# GPIO_Hat_v4_0_assignment.net
KiCad netlist of a schematic drawn in EAGLE
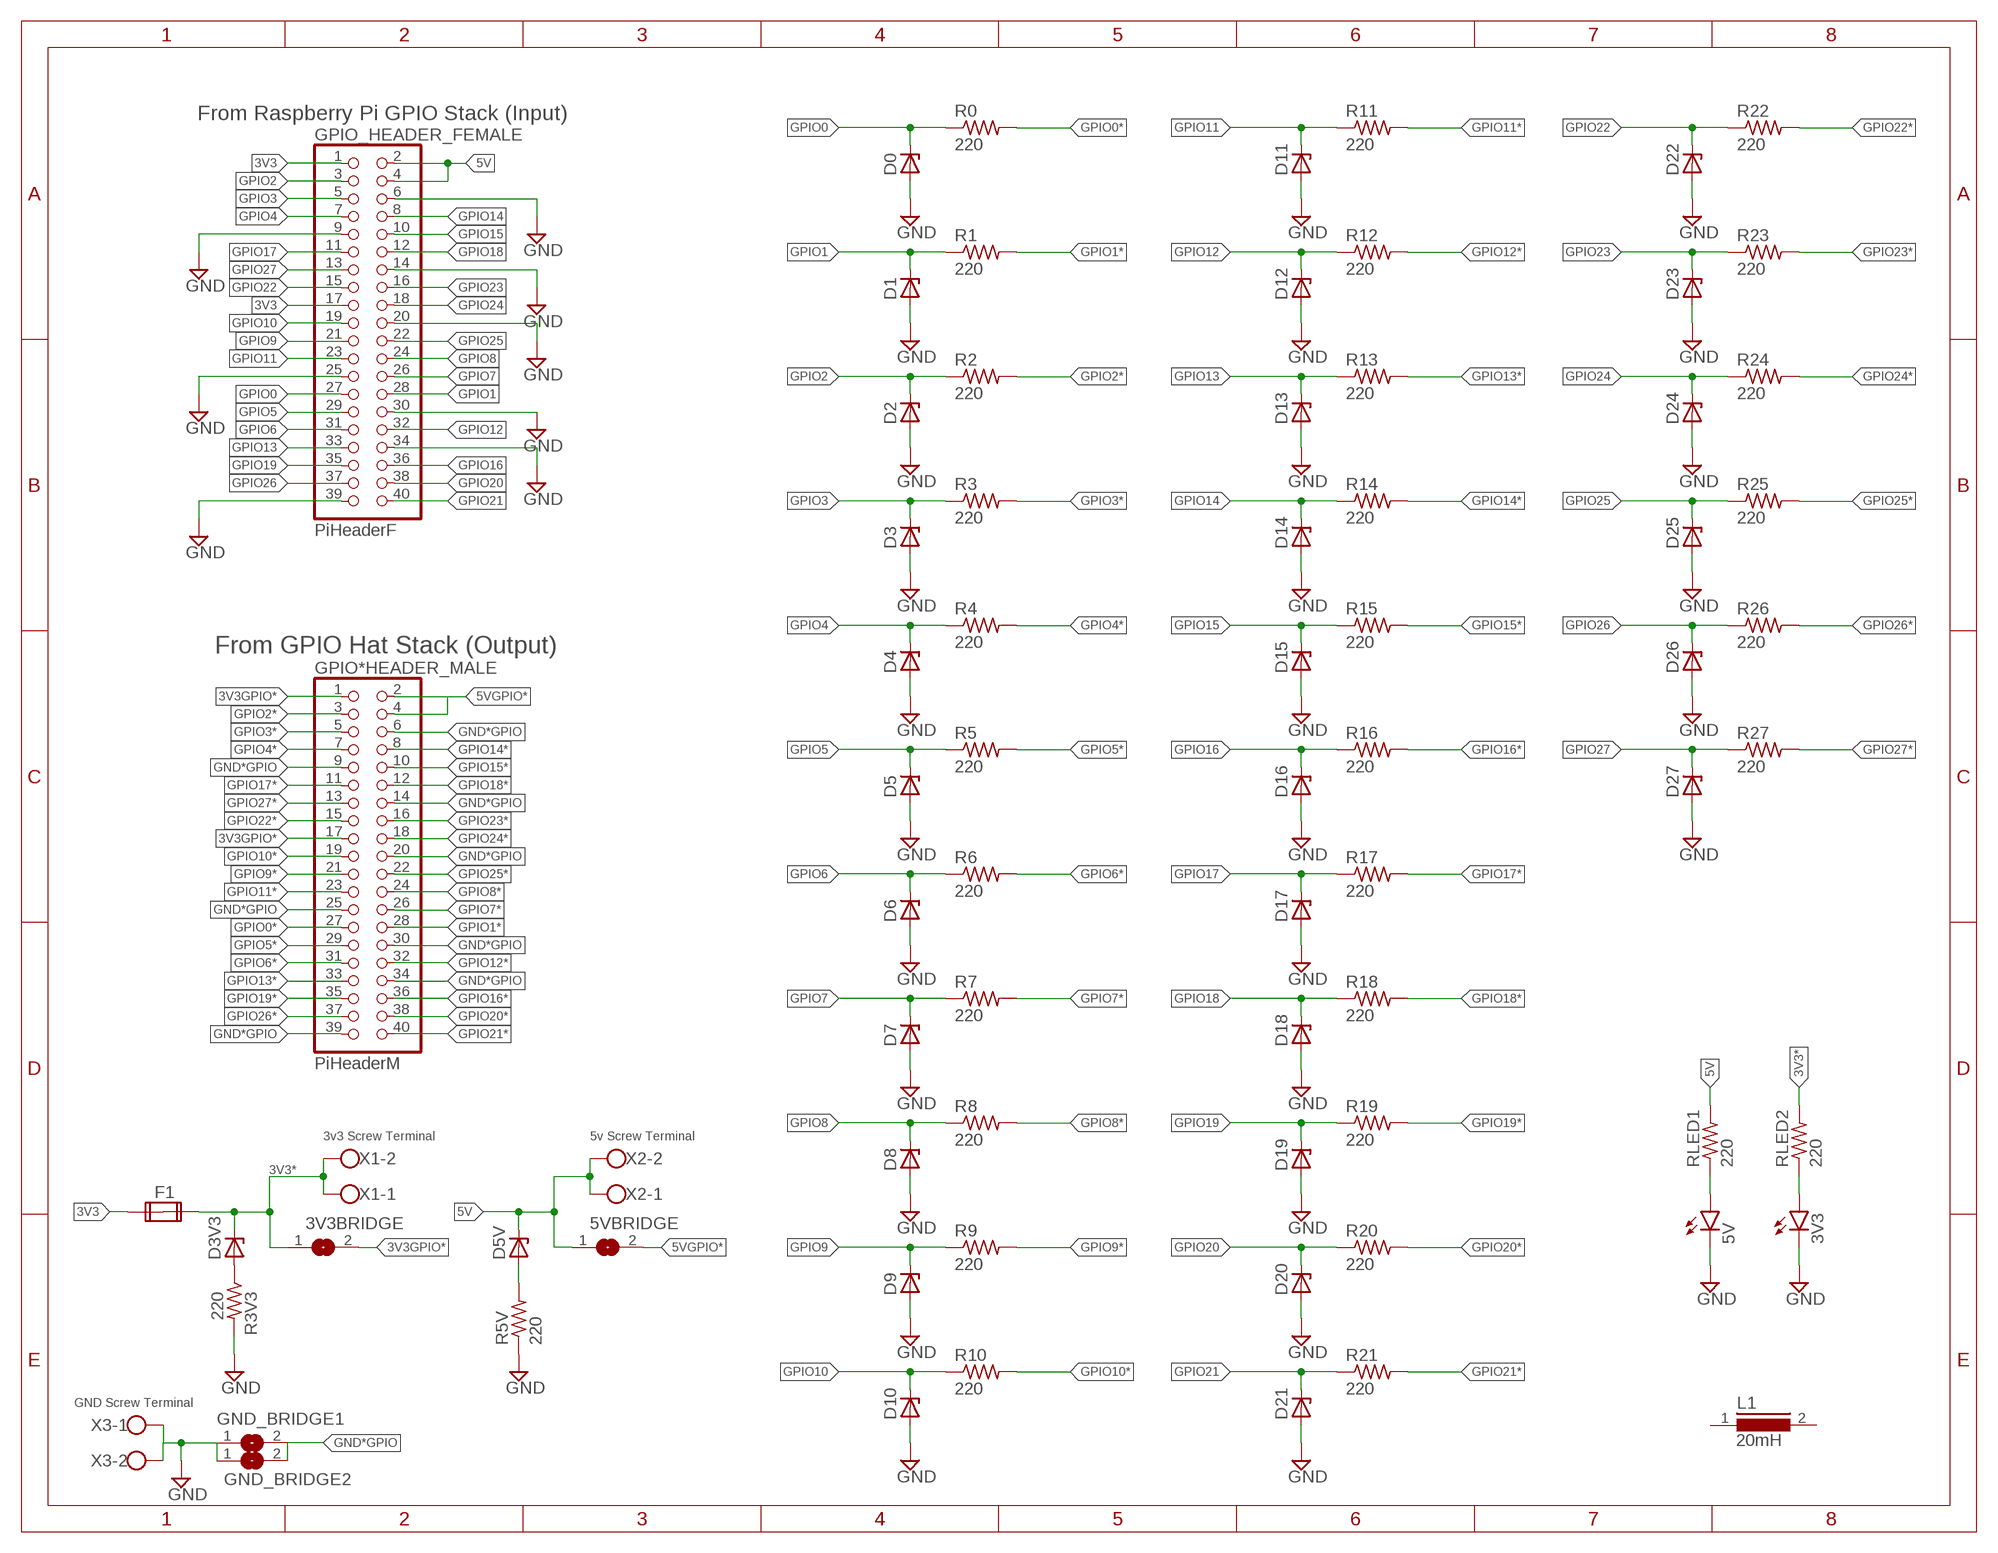
[diagram p0: schematic, sheet 1]

(export (version "E")
  (design (tool "Eeschema 10.0.6"))
  (components
    (comp (ref "3V3")
      (value "LED5MM")
      (footprint "eagle-import:LED5MM")
      (libsource (lib "eagle-import") (part "LED5MM"))
    )
    (comp (ref "3V3BRIDGE")
      (value "SJ")
      (footprint "eagle-import:SJ")
      (libsource (lib "eagle-import") (part "SJ"))
    )
    (comp (ref "5V")
      (value "LED5MM")
      (footprint "eagle-import:LED5MM")
      (libsource (lib "eagle-import") (part "LED5MM"))
    )
    (comp (ref "5VBRIDGE")
      (value "SJ")
      (footprint "eagle-import:SJ")
      (libsource (lib "eagle-import") (part "SJ"))
    )
    (comp (ref "D0")
      (value "1N4728")
      (footprint "eagle-import:DO41Z10")
      (fields (field (name "MF") "ON Semiconductor"))
      (libsource (lib "eagle-import") (part "1N4728"))
    )
    (comp (ref "D1")
      (value "1N4728")
      (footprint "eagle-import:DO41Z10")
      (fields (field (name "MF") "ON Semiconductor"))
      (libsource (lib "eagle-import") (part "1N4728"))
    )
    (comp (ref "D2")
      (value "1N4728")
      (footprint "eagle-import:DO41Z10")
      (fields (field (name "MF") "ON Semiconductor"))
      (libsource (lib "eagle-import") (part "1N4728"))
    )
    (comp (ref "D3")
      (value "1N4728")
      (footprint "eagle-import:DO41Z10")
      (fields (field (name "MF") "ON Semiconductor"))
      (libsource (lib "eagle-import") (part "1N4728"))
    )
    (comp (ref "D3V3")
      (value "1N4728")
      (footprint "eagle-import:DO41Z10")
      (fields (field (name "MF") "ON Semiconductor"))
      (libsource (lib "eagle-import") (part "1N4728"))
    )
    (comp (ref "D4")
      (value "1N4728")
      (footprint "eagle-import:DO41Z10")
      (fields (field (name "MF") "ON Semiconductor"))
      (libsource (lib "eagle-import") (part "1N4728"))
    )
    (comp (ref "D5")
      (value "1N4728")
      (footprint "eagle-import:DO41Z10")
      (fields (field (name "MF") "ON Semiconductor"))
      (libsource (lib "eagle-import") (part "1N4728"))
    )
    (comp (ref "D5V")
      (value "1N4728")
      (footprint "eagle-import:DO41Z10")
      (fields (field (name "MF") "ON Semiconductor"))
      (libsource (lib "eagle-import") (part "1N4728"))
    )
    (comp (ref "D6")
      (value "1N4728")
      (footprint "eagle-import:DO41Z10")
      (fields (field (name "MF") "ON Semiconductor"))
      (libsource (lib "eagle-import") (part "1N4728"))
    )
    (comp (ref "D7")
      (value "1N4728")
      (footprint "eagle-import:DO41Z10")
      (fields (field (name "MF") "ON Semiconductor"))
      (libsource (lib "eagle-import") (part "1N4728"))
    )
    (comp (ref "D8")
      (value "1N4728")
      (footprint "eagle-import:DO41Z10")
      (fields (field (name "MF") "ON Semiconductor"))
      (libsource (lib "eagle-import") (part "1N4728"))
    )
    (comp (ref "D9")
      (value "1N4728")
      (footprint "eagle-import:DO41Z10")
      (fields (field (name "MF") "ON Semiconductor"))
      (libsource (lib "eagle-import") (part "1N4728"))
    )
    (comp (ref "D10")
      (value "1N4728")
      (footprint "eagle-import:DO41Z10")
      (fields (field (name "MF") "ON Semiconductor"))
      (libsource (lib "eagle-import") (part "1N4728"))
    )
    (comp (ref "D11")
      (value "1N4728")
      (footprint "eagle-import:DO41Z10")
      (fields (field (name "MF") "ON Semiconductor"))
      (libsource (lib "eagle-import") (part "1N4728"))
    )
    (comp (ref "D12")
      (value "1N4728")
      (footprint "eagle-import:DO41Z10")
      (fields (field (name "MF") "ON Semiconductor"))
      (libsource (lib "eagle-import") (part "1N4728"))
    )
    (comp (ref "D13")
      (value "1N4728")
      (footprint "eagle-import:DO41Z10")
      (fields (field (name "MF") "ON Semiconductor"))
      (libsource (lib "eagle-import") (part "1N4728"))
    )
    (comp (ref "D14")
      (value "1N4728")
      (footprint "eagle-import:DO41Z10")
      (fields (field (name "MF") "ON Semiconductor"))
      (libsource (lib "eagle-import") (part "1N4728"))
    )
    (comp (ref "D15")
      (value "1N4728")
      (footprint "eagle-import:DO41Z10")
      (fields (field (name "MF") "ON Semiconductor"))
      (libsource (lib "eagle-import") (part "1N4728"))
    )
    (comp (ref "D16")
      (value "1N4728")
      (footprint "eagle-import:DO41Z10")
      (fields (field (name "MF") "ON Semiconductor"))
      (libsource (lib "eagle-import") (part "1N4728"))
    )
    (comp (ref "D17")
      (value "1N4728")
      (footprint "eagle-import:DO41Z10")
      (fields (field (name "MF") "ON Semiconductor"))
      (libsource (lib "eagle-import") (part "1N4728"))
    )
    (comp (ref "D18")
      (value "1N4728")
      (footprint "eagle-import:DO41Z10")
      (fields (field (name "MF") "ON Semiconductor"))
      (libsource (lib "eagle-import") (part "1N4728"))
    )
    (comp (ref "D19")
      (value "1N4728")
      (footprint "eagle-import:DO41Z10")
      (fields (field (name "MF") "ON Semiconductor"))
      (libsource (lib "eagle-import") (part "1N4728"))
    )
    (comp (ref "D20")
      (value "1N4728")
      (footprint "eagle-import:DO41Z10")
      (fields (field (name "MF") "ON Semiconductor"))
      (libsource (lib "eagle-import") (part "1N4728"))
    )
    (comp (ref "D21")
      (value "1N4728")
      (footprint "eagle-import:DO41Z10")
      (fields (field (name "MF") "ON Semiconductor"))
      (libsource (lib "eagle-import") (part "1N4728"))
    )
    (comp (ref "D22")
      (value "1N4728")
      (footprint "eagle-import:DO41Z10")
      (fields (field (name "MF") "ON Semiconductor"))
      (libsource (lib "eagle-import") (part "1N4728"))
    )
    (comp (ref "D23")
      (value "1N4728")
      (footprint "eagle-import:DO41Z10")
      (fields (field (name "MF") "ON Semiconductor"))
      (libsource (lib "eagle-import") (part "1N4728"))
    )
    (comp (ref "D24")
      (value "1N4728")
      (footprint "eagle-import:DO41Z10")
      (fields (field (name "MF") "ON Semiconductor"))
      (libsource (lib "eagle-import") (part "1N4728"))
    )
    (comp (ref "D25")
      (value "1N4728")
      (footprint "eagle-import:DO41Z10")
      (fields (field (name "MF") "ON Semiconductor"))
      (libsource (lib "eagle-import") (part "1N4728"))
    )
    (comp (ref "D26")
      (value "1N4728")
      (footprint "eagle-import:DO41Z10")
      (fields (field (name "MF") "ON Semiconductor"))
      (libsource (lib "eagle-import") (part "1N4728"))
    )
    (comp (ref "D27")
      (value "1N4728")
      (footprint "eagle-import:DO41Z10")
      (fields (field (name "MF") "ON Semiconductor"))
      (libsource (lib "eagle-import") (part "1N4728"))
    )
    (comp (ref "F1")
      (value "FUSE2P")
      (footprint "eagle-import:FUSE1")
      (libsource (lib "eagle-import") (part "FUSE2P"))
    )
    (comp (ref "GND_BRIDGE1")
      (value "SJ")
      (footprint "eagle-import:SJ")
      (libsource (lib "eagle-import") (part "SJ"))
    )
    (comp (ref "GND_BRIDGE2")
      (value "SJ")
      (footprint "eagle-import:SJ")
      (libsource (lib "eagle-import") (part "SJ"))
    )
    (comp (ref "GPIO*HEADER_MALE")
      (value "PiHeaderM")
      (footprint "eagle-import:2X20")
      (libsource (lib "eagle-import") (part "PINHD-2X20"))
    )
    (comp (ref "GPIO_HEADER_FEMALE")
      (value "PiHeaderF")
      (footprint "eagle-import:2X20")
      (libsource (lib "eagle-import") (part "PINHD-2X20"))
    )
    (comp (ref "L1")
      (value "20mH")
      (footprint "eagle-import:A26GFC")
      (libsource (lib "eagle-import") (part "A26GFC"))
    )
    (comp (ref "R0")
      (value "220")
      (footprint "eagle-import:0207_10")
      (libsource (lib "eagle-import") (part "rcl_334_R-US_0207/10"))
    )
    (comp (ref "R1")
      (value "220")
      (footprint "eagle-import:0207_10")
      (libsource (lib "eagle-import") (part "rcl_334_R-US_0207/10"))
    )
    (comp (ref "R2")
      (value "220")
      (footprint "eagle-import:0207_10")
      (libsource (lib "eagle-import") (part "rcl_334_R-US_0207/10"))
    )
    (comp (ref "R3")
      (value "220")
      (footprint "eagle-import:0207_10")
      (libsource (lib "eagle-import") (part "rcl_334_R-US_0207/10"))
    )
    (comp (ref "R3V3")
      (value "220")
      (footprint "eagle-import:0207_10")
      (libsource (lib "eagle-import") (part "rcl_334_R-US_0207/10"))
    )
    (comp (ref "R4")
      (value "220")
      (footprint "eagle-import:0207_10")
      (libsource (lib "eagle-import") (part "rcl_334_R-US_0207/10"))
    )
    (comp (ref "R5")
      (value "220")
      (footprint "eagle-import:0207_10")
      (libsource (lib "eagle-import") (part "rcl_334_R-US_0207/10"))
    )
    (comp (ref "R5V")
      (value "220")
      (footprint "eagle-import:0207_10")
      (libsource (lib "eagle-import") (part "rcl_334_R-US_0207/10"))
    )
    (comp (ref "R6")
      (value "220")
      (footprint "eagle-import:0207_10")
      (libsource (lib "eagle-import") (part "rcl_334_R-US_0207/10"))
    )
    (comp (ref "R7")
      (value "220")
      (footprint "eagle-import:0207_10")
      (libsource (lib "eagle-import") (part "rcl_334_R-US_0207/10"))
    )
    (comp (ref "R8")
      (value "220")
      (footprint "eagle-import:0207_10")
      (libsource (lib "eagle-import") (part "rcl_334_R-US_0207/10"))
    )
    (comp (ref "R9")
      (value "220")
      (footprint "eagle-import:0207_10")
      (libsource (lib "eagle-import") (part "rcl_334_R-US_0207/10"))
    )
    (comp (ref "R10")
      (value "220")
      (footprint "eagle-import:0207_10")
      (libsource (lib "eagle-import") (part "rcl_334_R-US_0207/10"))
    )
    (comp (ref "R11")
      (value "220")
      (footprint "eagle-import:0207_10")
      (libsource (lib "eagle-import") (part "rcl_334_R-US_0207/10"))
    )
    (comp (ref "R12")
      (value "220")
      (footprint "eagle-import:0207_10")
      (libsource (lib "eagle-import") (part "rcl_334_R-US_0207/10"))
    )
    (comp (ref "R13")
      (value "220")
      (footprint "eagle-import:0207_10")
      (libsource (lib "eagle-import") (part "rcl_334_R-US_0207/10"))
    )
    (comp (ref "R14")
      (value "220")
      (footprint "eagle-import:0207_10")
      (libsource (lib "eagle-import") (part "rcl_334_R-US_0207/10"))
    )
    (comp (ref "R15")
      (value "220")
      (footprint "eagle-import:0207_10")
      (libsource (lib "eagle-import") (part "rcl_334_R-US_0207/10"))
    )
    (comp (ref "R16")
      (value "220")
      (footprint "eagle-import:0207_10")
      (libsource (lib "eagle-import") (part "rcl_334_R-US_0207/10"))
    )
    (comp (ref "R17")
      (value "220")
      (footprint "eagle-import:0207_10")
      (libsource (lib "eagle-import") (part "rcl_334_R-US_0207/10"))
    )
    (comp (ref "R18")
      (value "220")
      (footprint "eagle-import:0207_10")
      (libsource (lib "eagle-import") (part "rcl_334_R-US_0207/10"))
    )
    (comp (ref "R19")
      (value "220")
      (footprint "eagle-import:0207_10")
      (libsource (lib "eagle-import") (part "rcl_334_R-US_0207/10"))
    )
    (comp (ref "R20")
      (value "220")
      (footprint "eagle-import:0207_10")
      (libsource (lib "eagle-import") (part "rcl_334_R-US_0207/10"))
    )
    (comp (ref "R21")
      (value "220")
      (footprint "eagle-import:0207_10")
      (libsource (lib "eagle-import") (part "rcl_334_R-US_0207/10"))
    )
    (comp (ref "R22")
      (value "220")
      (footprint "eagle-import:0207_10")
      (libsource (lib "eagle-import") (part "rcl_334_R-US_0207/10"))
    )
    (comp (ref "R23")
      (value "220")
      (footprint "eagle-import:0207_10")
      (libsource (lib "eagle-import") (part "rcl_334_R-US_0207/10"))
    )
    (comp (ref "R24")
      (value "220")
      (footprint "eagle-import:0207_10")
      (libsource (lib "eagle-import") (part "rcl_334_R-US_0207/10"))
    )
    (comp (ref "R25")
      (value "220")
      (footprint "eagle-import:0207_10")
      (libsource (lib "eagle-import") (part "rcl_334_R-US_0207/10"))
    )
    (comp (ref "R26")
      (value "220")
      (footprint "eagle-import:0207_10")
      (libsource (lib "eagle-import") (part "rcl_334_R-US_0207/10"))
    )
    (comp (ref "R27")
      (value "220")
      (footprint "eagle-import:0207_10")
      (libsource (lib "eagle-import") (part "rcl_334_R-US_0207/10"))
    )
    (comp (ref "RLED1")
      (value "220")
      (footprint "eagle-import:0207_10")
      (libsource (lib "eagle-import") (part "R-US_0207/10"))
    )
    (comp (ref "RLED2")
      (value "220")
      (footprint "eagle-import:0207_10")
      (libsource (lib "eagle-import") (part "R-US_0207/10"))
    )
    (comp (ref "X1")
      (value "W237-102")
      (footprint "eagle-import:W237-102")
      (fields (field (name "MPN") "237-102"))
      (libsource (lib "eagle-import") (part "W237-102"))
    )
    (comp (ref "X2")
      (value "W237-102")
      (footprint "eagle-import:W237-102")
      (fields (field (name "MPN") "237-102"))
      (libsource (lib "eagle-import") (part "W237-102"))
    )
    (comp (ref "X3")
      (value "W237-102")
      (footprint "eagle-import:W237-102")
      (fields (field (name "MPN") "237-102"))
      (libsource (lib "eagle-import") (part "W237-102"))
    )
  )
  (nets
    (net (code "1") (name "3V3") (class "Default")
      (node (ref "F1") (pin "1A") (pinfunction "1A_1A") (pintype "passive"))
      (node (ref "GPIO_HEADER_FEMALE") (pin "1") (pinfunction "1_1") (pintype "passive"))
      (node (ref "GPIO_HEADER_FEMALE") (pin "17") (pinfunction "17_17") (pintype "passive"))
    )
    (net (code "2") (name "3V3*") (class "Default")
      (node (ref "3V3BRIDGE") (pin "1") (pinfunction "1_1") (pintype "passive"))
      (node (ref "D3V3") (pin "C") (pinfunction "C_C") (pintype "passive"))
      (node (ref "F1") (pin "2A") (pinfunction "2A_2A") (pintype "passive"))
      (node (ref "RLED2") (pin "2") (pinfunction "2_2") (pintype "passive"))
      (node (ref "X1") (pin "1") (pinfunction "KL_1") (pintype "passive"))
      (node (ref "X1") (pin "2") (pinfunction "KL_2") (pintype "passive"))
    )
    (net (code "3") (name "3V3GPIO*") (class "Default")
      (node (ref "3V3BRIDGE") (pin "2") (pinfunction "2_2") (pintype "passive"))
      (node (ref "GPIO*HEADER_MALE") (pin "1") (pinfunction "1_1") (pintype "passive"))
      (node (ref "GPIO*HEADER_MALE") (pin "17") (pinfunction "17_17") (pintype "passive"))
    )
    (net (code "4") (name "5V") (class "Default")
      (node (ref "5VBRIDGE") (pin "1") (pinfunction "1_1") (pintype "passive"))
      (node (ref "D5V") (pin "C") (pinfunction "C_C") (pintype "passive"))
      (node (ref "GPIO_HEADER_FEMALE") (pin "2") (pinfunction "2_2") (pintype "passive"))
      (node (ref "GPIO_HEADER_FEMALE") (pin "4") (pinfunction "4_4") (pintype "passive"))
      (node (ref "RLED1") (pin "2") (pinfunction "2_2") (pintype "passive"))
      (node (ref "X2") (pin "1") (pinfunction "KL_1") (pintype "passive"))
      (node (ref "X2") (pin "2") (pinfunction "KL_2") (pintype "passive"))
    )
    (net (code "5") (name "5VGPIO*") (class "Default")
      (node (ref "5VBRIDGE") (pin "2") (pinfunction "2_2") (pintype "passive"))
      (node (ref "GPIO*HEADER_MALE") (pin "2") (pinfunction "2_2") (pintype "passive"))
      (node (ref "GPIO*HEADER_MALE") (pin "4") (pinfunction "4_4") (pintype "passive"))
    )
    (net (code "6") (name "GND") (class "Default")
      (node (ref "3V3") (pin "K") (pinfunction "C_K") (pintype "passive"))
      (node (ref "5V") (pin "K") (pinfunction "C_K") (pintype "passive"))
      (node (ref "D0") (pin "A") (pinfunction "A_A") (pintype "passive"))
      (node (ref "D1") (pin "A") (pinfunction "A_A") (pintype "passive"))
      (node (ref "D10") (pin "A") (pinfunction "A_A") (pintype "passive"))
      (node (ref "D11") (pin "A") (pinfunction "A_A") (pintype "passive"))
      (node (ref "D12") (pin "A") (pinfunction "A_A") (pintype "passive"))
      (node (ref "D13") (pin "A") (pinfunction "A_A") (pintype "passive"))
      (node (ref "D14") (pin "A") (pinfunction "A_A") (pintype "passive"))
      (node (ref "D15") (pin "A") (pinfunction "A_A") (pintype "passive"))
      (node (ref "D16") (pin "A") (pinfunction "A_A") (pintype "passive"))
      (node (ref "D17") (pin "A") (pinfunction "A_A") (pintype "passive"))
      (node (ref "D18") (pin "A") (pinfunction "A_A") (pintype "passive"))
      (node (ref "D19") (pin "A") (pinfunction "A_A") (pintype "passive"))
      (node (ref "D2") (pin "A") (pinfunction "A_A") (pintype "passive"))
      (node (ref "D20") (pin "A") (pinfunction "A_A") (pintype "passive"))
      (node (ref "D21") (pin "A") (pinfunction "A_A") (pintype "passive"))
      (node (ref "D22") (pin "A") (pinfunction "A_A") (pintype "passive"))
      (node (ref "D23") (pin "A") (pinfunction "A_A") (pintype "passive"))
      (node (ref "D24") (pin "A") (pinfunction "A_A") (pintype "passive"))
      (node (ref "D25") (pin "A") (pinfunction "A_A") (pintype "passive"))
      (node (ref "D26") (pin "A") (pinfunction "A_A") (pintype "passive"))
      (node (ref "D27") (pin "A") (pinfunction "A_A") (pintype "passive"))
      (node (ref "D3") (pin "A") (pinfunction "A_A") (pintype "passive"))
      (node (ref "D4") (pin "A") (pinfunction "A_A") (pintype "passive"))
      (node (ref "D5") (pin "A") (pinfunction "A_A") (pintype "passive"))
      (node (ref "D6") (pin "A") (pinfunction "A_A") (pintype "passive"))
      (node (ref "D7") (pin "A") (pinfunction "A_A") (pintype "passive"))
      (node (ref "D8") (pin "A") (pinfunction "A_A") (pintype "passive"))
      (node (ref "D9") (pin "A") (pinfunction "A_A") (pintype "passive"))
      (node (ref "GND_BRIDGE1") (pin "1") (pinfunction "1_1") (pintype "passive"))
      (node (ref "GND_BRIDGE2") (pin "1") (pinfunction "1_1") (pintype "passive"))
      (node (ref "GPIO_HEADER_FEMALE") (pin "14") (pinfunction "14_14") (pintype "passive"))
      (node (ref "GPIO_HEADER_FEMALE") (pin "20") (pinfunction "20_20") (pintype "passive"))
      (node (ref "GPIO_HEADER_FEMALE") (pin "25") (pinfunction "25_25") (pintype "passive"))
      (node (ref "GPIO_HEADER_FEMALE") (pin "30") (pinfunction "30_30") (pintype "passive"))
      (node (ref "GPIO_HEADER_FEMALE") (pin "34") (pinfunction "34_34") (pintype "passive"))
      (node (ref "GPIO_HEADER_FEMALE") (pin "39") (pinfunction "39_39") (pintype "passive"))
      (node (ref "GPIO_HEADER_FEMALE") (pin "6") (pinfunction "6_6") (pintype "passive"))
      (node (ref "GPIO_HEADER_FEMALE") (pin "9") (pinfunction "9_9") (pintype "passive"))
      (node (ref "R3V3") (pin "2") (pinfunction "2_2") (pintype "passive"))
      (node (ref "R5V") (pin "1") (pinfunction "1_1") (pintype "passive"))
      (node (ref "X3") (pin "1") (pinfunction "KL_1") (pintype "passive"))
      (node (ref "X3") (pin "2") (pinfunction "KL_2") (pintype "passive"))
    )
    (net (code "7") (name "GND*GPIO") (class "Default")
      (node (ref "GND_BRIDGE1") (pin "2") (pinfunction "2_2") (pintype "passive"))
      (node (ref "GND_BRIDGE2") (pin "2") (pinfunction "2_2") (pintype "passive"))
      (node (ref "GPIO*HEADER_MALE") (pin "14") (pinfunction "14_14") (pintype "passive"))
      (node (ref "GPIO*HEADER_MALE") (pin "20") (pinfunction "20_20") (pintype "passive"))
      (node (ref "GPIO*HEADER_MALE") (pin "25") (pinfunction "25_25") (pintype "passive"))
      (node (ref "GPIO*HEADER_MALE") (pin "30") (pinfunction "30_30") (pintype "passive"))
      (node (ref "GPIO*HEADER_MALE") (pin "34") (pinfunction "34_34") (pintype "passive"))
      (node (ref "GPIO*HEADER_MALE") (pin "39") (pinfunction "39_39") (pintype "passive"))
      (node (ref "GPIO*HEADER_MALE") (pin "6") (pinfunction "6_6") (pintype "passive"))
      (node (ref "GPIO*HEADER_MALE") (pin "9") (pinfunction "9_9") (pintype "passive"))
    )
    (net (code "8") (name "GPIO0") (class "Default")
      (node (ref "D0") (pin "C") (pinfunction "C_C") (pintype "passive"))
      (node (ref "GPIO_HEADER_FEMALE") (pin "27") (pinfunction "27_27") (pintype "passive"))
      (node (ref "R0") (pin "1") (pinfunction "1_1") (pintype "passive"))
    )
    (net (code "9") (name "GPIO0*") (class "Default")
      (node (ref "GPIO*HEADER_MALE") (pin "27") (pinfunction "27_27") (pintype "passive"))
      (node (ref "R0") (pin "2") (pinfunction "2_2") (pintype "passive"))
    )
    (net (code "10") (name "GPIO1") (class "Default")
      (node (ref "D1") (pin "C") (pinfunction "C_C") (pintype "passive"))
      (node (ref "GPIO_HEADER_FEMALE") (pin "28") (pinfunction "28_28") (pintype "passive"))
      (node (ref "R1") (pin "1") (pinfunction "1_1") (pintype "passive"))
    )
    (net (code "11") (name "GPIO1*") (class "Default")
      (node (ref "GPIO*HEADER_MALE") (pin "28") (pinfunction "28_28") (pintype "passive"))
      (node (ref "R1") (pin "2") (pinfunction "2_2") (pintype "passive"))
    )
    (net (code "12") (name "GPIO2") (class "Default")
      (node (ref "D2") (pin "C") (pinfunction "C_C") (pintype "passive"))
      (node (ref "GPIO_HEADER_FEMALE") (pin "3") (pinfunction "3_3") (pintype "passive"))
      (node (ref "R2") (pin "1") (pinfunction "1_1") (pintype "passive"))
    )
    (net (code "13") (name "GPIO2*") (class "Default")
      (node (ref "GPIO*HEADER_MALE") (pin "3") (pinfunction "3_3") (pintype "passive"))
      (node (ref "R2") (pin "2") (pinfunction "2_2") (pintype "passive"))
    )
    (net (code "14") (name "GPIO3") (class "Default")
      (node (ref "D3") (pin "C") (pinfunction "C_C") (pintype "passive"))
      (node (ref "GPIO_HEADER_FEMALE") (pin "5") (pinfunction "5_5") (pintype "passive"))
      (node (ref "R3") (pin "1") (pinfunction "1_1") (pintype "passive"))
    )
    (net (code "15") (name "GPIO3*") (class "Default")
      (node (ref "GPIO*HEADER_MALE") (pin "5") (pinfunction "5_5") (pintype "passive"))
      (node (ref "R3") (pin "2") (pinfunction "2_2") (pintype "passive"))
    )
    (net (code "16") (name "GPIO4") (class "Default")
      (node (ref "D4") (pin "C") (pinfunction "C_C") (pintype "passive"))
      (node (ref "GPIO_HEADER_FEMALE") (pin "7") (pinfunction "7_7") (pintype "passive"))
      (node (ref "R4") (pin "1") (pinfunction "1_1") (pintype "passive"))
    )
    (net (code "17") (name "GPIO4*") (class "Default")
      (node (ref "GPIO*HEADER_MALE") (pin "7") (pinfunction "7_7") (pintype "passive"))
      (node (ref "R4") (pin "2") (pinfunction "2_2") (pintype "passive"))
    )
    (net (code "18") (name "GPIO5") (class "Default")
      (node (ref "D5") (pin "C") (pinfunction "C_C") (pintype "passive"))
      (node (ref "GPIO_HEADER_FEMALE") (pin "29") (pinfunction "29_29") (pintype "passive"))
      (node (ref "R5") (pin "1") (pinfunction "1_1") (pintype "passive"))
    )
    (net (code "19") (name "GPIO5*") (class "Default")
      (node (ref "GPIO*HEADER_MALE") (pin "29") (pinfunction "29_29") (pintype "passive"))
      (node (ref "R5") (pin "2") (pinfunction "2_2") (pintype "passive"))
    )
    (net (code "20") (name "GPIO6") (class "Default")
      (node (ref "D6") (pin "C") (pinfunction "C_C") (pintype "passive"))
      (node (ref "GPIO_HEADER_FEMALE") (pin "31") (pinfunction "31_31") (pintype "passive"))
      (node (ref "R6") (pin "1") (pinfunction "1_1") (pintype "passive"))
    )
    (net (code "21") (name "GPIO6*") (class "Default")
      (node (ref "GPIO*HEADER_MALE") (pin "31") (pinfunction "31_31") (pintype "passive"))
      (node (ref "R6") (pin "2") (pinfunction "2_2") (pintype "passive"))
    )
    (net (code "22") (name "GPIO7") (class "Default")
      (node (ref "D7") (pin "C") (pinfunction "C_C") (pintype "passive"))
      (node (ref "GPIO_HEADER_FEMALE") (pin "26") (pinfunction "26_26") (pintype "passive"))
      (node (ref "R7") (pin "1") (pinfunction "1_1") (pintype "passive"))
    )
    (net (code "23") (name "GPIO7*") (class "Default")
      (node (ref "GPIO*HEADER_MALE") (pin "26") (pinfunction "26_26") (pintype "passive"))
      (node (ref "R7") (pin "2") (pinfunction "2_2") (pintype "passive"))
    )
    (net (code "24") (name "GPIO8") (class "Default")
      (node (ref "D8") (pin "C") (pinfunction "C_C") (pintype "passive"))
      (node (ref "GPIO_HEADER_FEMALE") (pin "24") (pinfunction "24_24") (pintype "passive"))
      (node (ref "R8") (pin "1") (pinfunction "1_1") (pintype "passive"))
    )
    (net (code "25") (name "GPIO8*") (class "Default")
      (node (ref "GPIO*HEADER_MALE") (pin "24") (pinfunction "24_24") (pintype "passive"))
      (node (ref "R8") (pin "2") (pinfunction "2_2") (pintype "passive"))
    )
    (net (code "26") (name "GPIO9") (class "Default")
      (node (ref "D9") (pin "C") (pinfunction "C_C") (pintype "passive"))
      (node (ref "GPIO_HEADER_FEMALE") (pin "21") (pinfunction "21_21") (pintype "passive"))
      (node (ref "R9") (pin "1") (pinfunction "1_1") (pintype "passive"))
    )
    (net (code "27") (name "GPIO9*") (class "Default")
      (node (ref "GPIO*HEADER_MALE") (pin "21") (pinfunction "21_21") (pintype "passive"))
      (node (ref "R9") (pin "2") (pinfunction "2_2") (pintype "passive"))
    )
    (net (code "28") (name "GPIO10") (class "Default")
      (node (ref "D10") (pin "C") (pinfunction "C_C") (pintype "passive"))
      (node (ref "GPIO_HEADER_FEMALE") (pin "19") (pinfunction "19_19") (pintype "passive"))
      (node (ref "R10") (pin "1") (pinfunction "1_1") (pintype "passive"))
    )
    (net (code "29") (name "GPIO10*") (class "Default")
      (node (ref "GPIO*HEADER_MALE") (pin "19") (pinfunction "19_19") (pintype "passive"))
      (node (ref "R10") (pin "2") (pinfunction "2_2") (pintype "passive"))
    )
    (net (code "30") (name "GPIO11") (class "Default")
      (node (ref "D11") (pin "C") (pinfunction "C_C") (pintype "passive"))
      (node (ref "GPIO_HEADER_FEMALE") (pin "23") (pinfunction "23_23") (pintype "passive"))
      (node (ref "R11") (pin "1") (pinfunction "1_1") (pintype "passive"))
    )
    (net (code "31") (name "GPIO11*") (class "Default")
      (node (ref "GPIO*HEADER_MALE") (pin "23") (pinfunction "23_23") (pintype "passive"))
      (node (ref "R11") (pin "2") (pinfunction "2_2") (pintype "passive"))
    )
    (net (code "32") (name "GPIO12") (class "Default")
      (node (ref "D12") (pin "C") (pinfunction "C_C") (pintype "passive"))
      (node (ref "GPIO_HEADER_FEMALE") (pin "32") (pinfunction "32_32") (pintype "passive"))
      (node (ref "R12") (pin "1") (pinfunction "1_1") (pintype "passive"))
    )
    (net (code "33") (name "GPIO12*") (class "Default")
      (node (ref "GPIO*HEADER_MALE") (pin "32") (pinfunction "32_32") (pintype "passive"))
      (node (ref "R12") (pin "2") (pinfunction "2_2") (pintype "passive"))
    )
    (net (code "34") (name "GPIO13") (class "Default")
      (node (ref "D13") (pin "C") (pinfunction "C_C") (pintype "passive"))
      (node (ref "GPIO_HEADER_FEMALE") (pin "33") (pinfunction "33_33") (pintype "passive"))
      (node (ref "R13") (pin "1") (pinfunction "1_1") (pintype "passive"))
    )
    (net (code "35") (name "GPIO13*") (class "Default")
      (node (ref "GPIO*HEADER_MALE") (pin "33") (pinfunction "33_33") (pintype "passive"))
      (node (ref "R13") (pin "2") (pinfunction "2_2") (pintype "passive"))
    )
    (net (code "36") (name "GPIO14") (class "Default")
      (node (ref "D14") (pin "C") (pinfunction "C_C") (pintype "passive"))
      (node (ref "GPIO_HEADER_FEMALE") (pin "8") (pinfunction "8_8") (pintype "passive"))
      (node (ref "R14") (pin "1") (pinfunction "1_1") (pintype "passive"))
    )
    (net (code "37") (name "GPIO14*") (class "Default")
      (node (ref "GPIO*HEADER_MALE") (pin "8") (pinfunction "8_8") (pintype "passive"))
      (node (ref "R14") (pin "2") (pinfunction "2_2") (pintype "passive"))
    )
    (net (code "38") (name "GPIO15") (class "Default")
      (node (ref "D15") (pin "C") (pinfunction "C_C") (pintype "passive"))
      (node (ref "GPIO_HEADER_FEMALE") (pin "10") (pinfunction "10_10") (pintype "passive"))
      (node (ref "R15") (pin "1") (pinfunction "1_1") (pintype "passive"))
    )
    (net (code "39") (name "GPIO15*") (class "Default")
      (node (ref "GPIO*HEADER_MALE") (pin "10") (pinfunction "10_10") (pintype "passive"))
      (node (ref "R15") (pin "2") (pinfunction "2_2") (pintype "passive"))
    )
    (net (code "40") (name "GPIO16") (class "Default")
      (node (ref "D16") (pin "C") (pinfunction "C_C") (pintype "passive"))
      (node (ref "GPIO_HEADER_FEMALE") (pin "36") (pinfunction "36_36") (pintype "passive"))
      (node (ref "R16") (pin "1") (pinfunction "1_1") (pintype "passive"))
    )
    (net (code "41") (name "GPIO16*") (class "Default")
      (node (ref "GPIO*HEADER_MALE") (pin "36") (pinfunction "36_36") (pintype "passive"))
      (node (ref "R16") (pin "2") (pinfunction "2_2") (pintype "passive"))
    )
    (net (code "42") (name "GPIO17") (class "Default")
      (node (ref "D17") (pin "C") (pinfunction "C_C") (pintype "passive"))
      (node (ref "GPIO_HEADER_FEMALE") (pin "11") (pinfunction "11_11") (pintype "passive"))
      (node (ref "R17") (pin "1") (pinfunction "1_1") (pintype "passive"))
    )
    (net (code "43") (name "GPIO17*") (class "Default")
      (node (ref "GPIO*HEADER_MALE") (pin "11") (pinfunction "11_11") (pintype "passive"))
      (node (ref "R17") (pin "2") (pinfunction "2_2") (pintype "passive"))
    )
    (net (code "44") (name "GPIO18") (class "Default")
      (node (ref "D18") (pin "C") (pinfunction "C_C") (pintype "passive"))
      (node (ref "GPIO_HEADER_FEMALE") (pin "12") (pinfunction "12_12") (pintype "passive"))
      (node (ref "R18") (pin "1") (pinfunction "1_1") (pintype "passive"))
    )
    (net (code "45") (name "GPIO18*") (class "Default")
      (node (ref "GPIO*HEADER_MALE") (pin "12") (pinfunction "12_12") (pintype "passive"))
      (node (ref "R18") (pin "2") (pinfunction "2_2") (pintype "passive"))
    )
    (net (code "46") (name "GPIO19") (class "Default")
      (node (ref "D19") (pin "C") (pinfunction "C_C") (pintype "passive"))
      (node (ref "GPIO_HEADER_FEMALE") (pin "35") (pinfunction "35_35") (pintype "passive"))
      (node (ref "R19") (pin "1") (pinfunction "1_1") (pintype "passive"))
    )
    (net (code "47") (name "GPIO19*") (class "Default")
      (node (ref "GPIO*HEADER_MALE") (pin "35") (pinfunction "35_35") (pintype "passive"))
      (node (ref "R19") (pin "2") (pinfunction "2_2") (pintype "passive"))
    )
    (net (code "48") (name "GPIO20") (class "Default")
      (node (ref "D20") (pin "C") (pinfunction "C_C") (pintype "passive"))
      (node (ref "GPIO_HEADER_FEMALE") (pin "38") (pinfunction "38_38") (pintype "passive"))
      (node (ref "R20") (pin "1") (pinfunction "1_1") (pintype "passive"))
    )
    (net (code "49") (name "GPIO20*") (class "Default")
      (node (ref "GPIO*HEADER_MALE") (pin "38") (pinfunction "38_38") (pintype "passive"))
      (node (ref "R20") (pin "2") (pinfunction "2_2") (pintype "passive"))
    )
    (net (code "50") (name "GPIO21") (class "Default")
      (node (ref "D21") (pin "C") (pinfunction "C_C") (pintype "passive"))
      (node (ref "GPIO_HEADER_FEMALE") (pin "40") (pinfunction "40_40") (pintype "passive"))
      (node (ref "R21") (pin "1") (pinfunction "1_1") (pintype "passive"))
    )
    (net (code "51") (name "GPIO21*") (class "Default")
      (node (ref "GPIO*HEADER_MALE") (pin "40") (pinfunction "40_40") (pintype "passive"))
      (node (ref "R21") (pin "2") (pinfunction "2_2") (pintype "passive"))
    )
    (net (code "52") (name "GPIO22") (class "Default")
      (node (ref "D22") (pin "C") (pinfunction "C_C") (pintype "passive"))
      (node (ref "GPIO_HEADER_FEMALE") (pin "15") (pinfunction "15_15") (pintype "passive"))
      (node (ref "R22") (pin "1") (pinfunction "1_1") (pintype "passive"))
    )
    (net (code "53") (name "GPIO22*") (class "Default")
      (node (ref "GPIO*HEADER_MALE") (pin "15") (pinfunction "15_15") (pintype "passive"))
      (node (ref "R22") (pin "2") (pinfunction "2_2") (pintype "passive"))
    )
    (net (code "54") (name "GPIO23") (class "Default")
      (node (ref "D23") (pin "C") (pinfunction "C_C") (pintype "passive"))
      (node (ref "GPIO_HEADER_FEMALE") (pin "16") (pinfunction "16_16") (pintype "passive"))
      (node (ref "R23") (pin "1") (pinfunction "1_1") (pintype "passive"))
    )
    (net (code "55") (name "GPIO23*") (class "Default")
      (node (ref "GPIO*HEADER_MALE") (pin "16") (pinfunction "16_16") (pintype "passive"))
      (node (ref "R23") (pin "2") (pinfunction "2_2") (pintype "passive"))
    )
    (net (code "56") (name "GPIO24") (class "Default")
      (node (ref "D24") (pin "C") (pinfunction "C_C") (pintype "passive"))
      (node (ref "GPIO_HEADER_FEMALE") (pin "18") (pinfunction "18_18") (pintype "passive"))
      (node (ref "R24") (pin "1") (pinfunction "1_1") (pintype "passive"))
    )
    (net (code "57") (name "GPIO24*") (class "Default")
      (node (ref "GPIO*HEADER_MALE") (pin "18") (pinfunction "18_18") (pintype "passive"))
      (node (ref "R24") (pin "2") (pinfunction "2_2") (pintype "passive"))
    )
    (net (code "58") (name "GPIO25") (class "Default")
      (node (ref "D25") (pin "C") (pinfunction "C_C") (pintype "passive"))
      (node (ref "GPIO_HEADER_FEMALE") (pin "22") (pinfunction "22_22") (pintype "passive"))
      (node (ref "R25") (pin "1") (pinfunction "1_1") (pintype "passive"))
    )
    (net (code "59") (name "GPIO25*") (class "Default")
      (node (ref "GPIO*HEADER_MALE") (pin "22") (pinfunction "22_22") (pintype "passive"))
      (node (ref "R25") (pin "2") (pinfunction "2_2") (pintype "passive"))
    )
    (net (code "60") (name "GPIO26") (class "Default")
      (node (ref "D26") (pin "C") (pinfunction "C_C") (pintype "passive"))
      (node (ref "GPIO_HEADER_FEMALE") (pin "37") (pinfunction "37_37") (pintype "passive"))
      (node (ref "R26") (pin "1") (pinfunction "1_1") (pintype "passive"))
    )
    (net (code "61") (name "GPIO26*") (class "Default")
      (node (ref "GPIO*HEADER_MALE") (pin "37") (pinfunction "37_37") (pintype "passive"))
      (node (ref "R26") (pin "2") (pinfunction "2_2") (pintype "passive"))
    )
    (net (code "62") (name "GPIO27") (class "Default")
      (node (ref "D27") (pin "C") (pinfunction "C_C") (pintype "passive"))
      (node (ref "GPIO_HEADER_FEMALE") (pin "13") (pinfunction "13_13") (pintype "passive"))
      (node (ref "R27") (pin "1") (pinfunction "1_1") (pintype "passive"))
    )
    (net (code "63") (name "GPIO27*") (class "Default")
      (node (ref "GPIO*HEADER_MALE") (pin "13") (pinfunction "13_13") (pintype "passive"))
      (node (ref "R27") (pin "2") (pinfunction "2_2") (pintype "passive"))
    )
    (net (code "64") (name "Net-(3V3-PadA)") (class "Default")
      (node (ref "3V3") (pin "A") (pinfunction "A_A") (pintype "passive"))
      (node (ref "RLED2") (pin "1") (pinfunction "1_1") (pintype "passive"))
    )
    (net (code "65") (name "Net-(5V-PadA)") (class "Default")
      (node (ref "5V") (pin "A") (pinfunction "A_A") (pintype "passive"))
      (node (ref "RLED1") (pin "1") (pinfunction "1_1") (pintype "passive"))
    )
    (net (code "66") (name "Net-(D3V3-PadA)") (class "Default")
      (node (ref "D3V3") (pin "A") (pinfunction "A_A") (pintype "passive"))
      (node (ref "R3V3") (pin "1") (pinfunction "1_1") (pintype "passive"))
    )
    (net (code "67") (name "Net-(D5V-PadA)") (class "Default")
      (node (ref "D5V") (pin "A") (pinfunction "A_A") (pintype "passive"))
      (node (ref "R5V") (pin "2") (pinfunction "2_2") (pintype "passive"))
    )
    (net (code "68") (name "unconnected-(F1-Pad1B)") (class "Default")
      (node (ref "F1") (pin "1B") (pinfunction "1B_1B") (pintype "passive"))
    )
    (net (code "69") (name "unconnected-(F1-Pad2B)") (class "Default")
      (node (ref "F1") (pin "2B") (pinfunction "2B_2B") (pintype "passive"))
    )
    (net (code "70") (name "unconnected-(L1-Pad1)") (class "Default")
      (node (ref "L1") (pin "1") (pinfunction "1_1") (pintype "passive"))
    )
    (net (code "71") (name "unconnected-(L1-Pad2)") (class "Default")
      (node (ref "L1") (pin "2") (pinfunction "2_2") (pintype "passive"))
    )
  )
)
